# Water_Level_Sensor.net
KiCad netlist of a schematic drawn in EAGLE
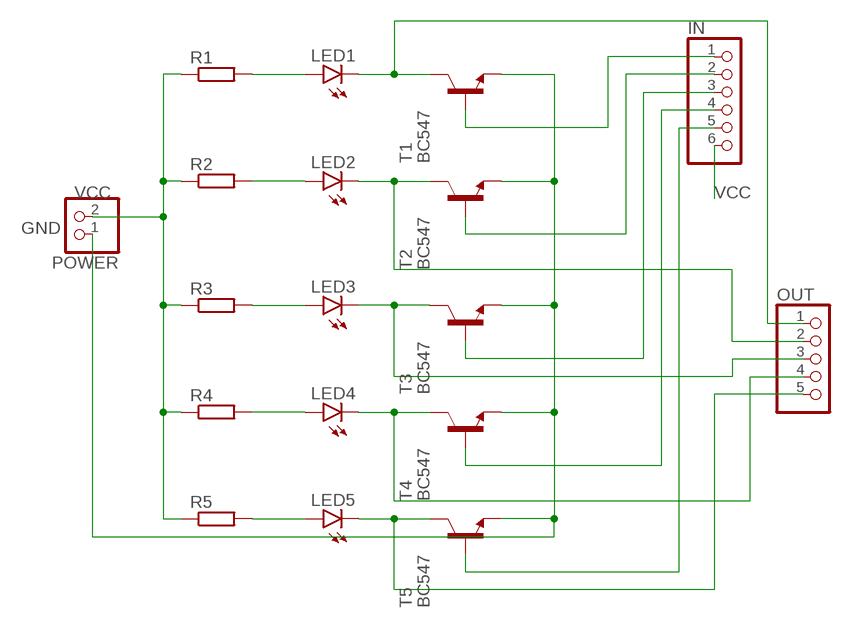
[diagram p0: schematic, sheet 1]

(export (version "E")
  (design (tool "Eeschema 10.0.6"))
  (components
    (comp (ref "IN")
      (value "PINHD-1X6")
      (footprint "eagle-import:1X06")
      (libsource (lib "eagle-import") (part "PINHD-1X6"))
    )
    (comp (ref "LED1")
      (value "LED5MM")
      (footprint "eagle-import:LED5MM")
      (libsource (lib "eagle-import") (part "LED5MM"))
    )
    (comp (ref "LED2")
      (value "LED5MM")
      (footprint "eagle-import:LED5MM")
      (libsource (lib "eagle-import") (part "LED5MM"))
    )
    (comp (ref "LED3")
      (value "LED5MM")
      (footprint "eagle-import:LED5MM")
      (libsource (lib "eagle-import") (part "LED5MM"))
    )
    (comp (ref "LED4")
      (value "LED5MM")
      (footprint "eagle-import:LED5MM")
      (libsource (lib "eagle-import") (part "LED5MM"))
    )
    (comp (ref "LED5")
      (value "LED5MM")
      (footprint "eagle-import:LED5MM")
      (libsource (lib "eagle-import") (part "LED5MM"))
    )
    (comp (ref "OUT")
      (value "PINHD-1X5")
      (footprint "eagle-import:1X05")
      (libsource (lib "eagle-import") (part "PINHD-1X5"))
    )
    (comp (ref "POWER")
      (value "PINHD-1X2")
      (footprint "eagle-import:1X02")
      (libsource (lib "eagle-import") (part "PINHD-1X2"))
    )
    (comp (ref "R1")
      (value "R-EU_0204/7")
      (footprint "eagle-import:0204_7")
      (libsource (lib "eagle-import") (part "R-EU_0204/7"))
    )
    (comp (ref "R2")
      (value "R-EU_0204/7")
      (footprint "eagle-import:0204_7")
      (libsource (lib "eagle-import") (part "R-EU_0204/7"))
    )
    (comp (ref "R3")
      (value "R-EU_0204/7")
      (footprint "eagle-import:0204_7")
      (libsource (lib "eagle-import") (part "R-EU_0204/7"))
    )
    (comp (ref "R4")
      (value "R-EU_0204/7")
      (footprint "eagle-import:0204_7")
      (libsource (lib "eagle-import") (part "R-EU_0204/7"))
    )
    (comp (ref "R5")
      (value "R-EU_0204/7")
      (footprint "eagle-import:0204_7")
      (libsource (lib "eagle-import") (part "R-EU_0204/7"))
    )
    (comp (ref "T1")
      (value "BC547")
      (footprint "eagle-import:TO92")
      (libsource (lib "eagle-import") (part "BC547"))
    )
    (comp (ref "T2")
      (value "BC547")
      (footprint "eagle-import:TO92")
      (libsource (lib "eagle-import") (part "BC547"))
    )
    (comp (ref "T3")
      (value "BC547")
      (footprint "eagle-import:TO92")
      (libsource (lib "eagle-import") (part "BC547"))
    )
    (comp (ref "T4")
      (value "BC547")
      (footprint "eagle-import:TO92")
      (libsource (lib "eagle-import") (part "BC547"))
    )
    (comp (ref "T5")
      (value "BC547")
      (footprint "eagle-import:TO92")
      (libsource (lib "eagle-import") (part "BC547"))
    )
  )
  (nets
    (net (code "1") (name "/GND") (class "Default")
      (node (ref "POWER") (pin "1") (pinfunction "1_1") (pintype "passive"))
      (node (ref "T1") (pin "1") (pinfunction "E_1") (pintype "passive"))
      (node (ref "T2") (pin "1") (pinfunction "E_1") (pintype "passive"))
      (node (ref "T3") (pin "1") (pinfunction "E_1") (pintype "passive"))
      (node (ref "T4") (pin "1") (pinfunction "E_1") (pintype "passive"))
      (node (ref "T5") (pin "1") (pinfunction "E_1") (pintype "passive"))
    )
    (net (code "2") (name "/VCC") (class "Default")
      (node (ref "IN") (pin "6") (pinfunction "6_6") (pintype "passive"))
      (node (ref "POWER") (pin "2") (pinfunction "2_2") (pintype "passive"))
      (node (ref "R1") (pin "1") (pinfunction "1_1") (pintype "passive"))
      (node (ref "R2") (pin "1") (pinfunction "1_1") (pintype "passive"))
      (node (ref "R3") (pin "1") (pinfunction "1_1") (pintype "passive"))
      (node (ref "R4") (pin "1") (pinfunction "1_1") (pintype "passive"))
      (node (ref "R5") (pin "1") (pinfunction "1_1") (pintype "passive"))
    )
    (net (code "3") (name "Net-(LED1-C)") (class "Default")
      (node (ref "LED1") (pin "K") (pinfunction "C_K") (pintype "passive"))
      (node (ref "OUT") (pin "1") (pinfunction "1_1") (pintype "passive"))
      (node (ref "T1") (pin "3") (pinfunction "C_3") (pintype "passive"))
    )
    (net (code "4") (name "Net-(LED1-PadA)") (class "Default")
      (node (ref "LED1") (pin "A") (pinfunction "A_A") (pintype "passive"))
      (node (ref "R1") (pin "2") (pinfunction "2_2") (pintype "passive"))
    )
    (net (code "5") (name "Net-(LED2-C)") (class "Default")
      (node (ref "LED2") (pin "K") (pinfunction "C_K") (pintype "passive"))
      (node (ref "OUT") (pin "2") (pinfunction "2_2") (pintype "passive"))
      (node (ref "T2") (pin "3") (pinfunction "C_3") (pintype "passive"))
    )
    (net (code "6") (name "Net-(LED2-PadA)") (class "Default")
      (node (ref "LED2") (pin "A") (pinfunction "A_A") (pintype "passive"))
      (node (ref "R2") (pin "2") (pinfunction "2_2") (pintype "passive"))
    )
    (net (code "7") (name "Net-(LED3-C)") (class "Default")
      (node (ref "LED3") (pin "K") (pinfunction "C_K") (pintype "passive"))
      (node (ref "OUT") (pin "3") (pinfunction "3_3") (pintype "passive"))
      (node (ref "T3") (pin "3") (pinfunction "C_3") (pintype "passive"))
    )
    (net (code "8") (name "Net-(LED3-PadA)") (class "Default")
      (node (ref "LED3") (pin "A") (pinfunction "A_A") (pintype "passive"))
      (node (ref "R3") (pin "2") (pinfunction "2_2") (pintype "passive"))
    )
    (net (code "9") (name "Net-(LED4-C)") (class "Default")
      (node (ref "LED4") (pin "K") (pinfunction "C_K") (pintype "passive"))
      (node (ref "OUT") (pin "4") (pinfunction "4_4") (pintype "passive"))
      (node (ref "T4") (pin "3") (pinfunction "C_3") (pintype "passive"))
    )
    (net (code "10") (name "Net-(LED4-PadA)") (class "Default")
      (node (ref "LED4") (pin "A") (pinfunction "A_A") (pintype "passive"))
      (node (ref "R4") (pin "2") (pinfunction "2_2") (pintype "passive"))
    )
    (net (code "11") (name "Net-(LED5-C)") (class "Default")
      (node (ref "LED5") (pin "K") (pinfunction "C_K") (pintype "passive"))
      (node (ref "OUT") (pin "5") (pinfunction "5_5") (pintype "passive"))
      (node (ref "T5") (pin "3") (pinfunction "C_3") (pintype "passive"))
    )
    (net (code "12") (name "Net-(LED5-PadA)") (class "Default")
      (node (ref "LED5") (pin "A") (pinfunction "A_A") (pintype "passive"))
      (node (ref "R5") (pin "2") (pinfunction "2_2") (pintype "passive"))
    )
    (net (code "13") (name "Net-(T1-B)") (class "Default")
      (node (ref "IN") (pin "1") (pinfunction "1_1") (pintype "passive"))
      (node (ref "T1") (pin "2") (pinfunction "B_2") (pintype "passive"))
    )
    (net (code "14") (name "Net-(T2-B)") (class "Default")
      (node (ref "IN") (pin "2") (pinfunction "2_2") (pintype "passive"))
      (node (ref "T2") (pin "2") (pinfunction "B_2") (pintype "passive"))
    )
    (net (code "15") (name "Net-(T3-B)") (class "Default")
      (node (ref "IN") (pin "3") (pinfunction "3_3") (pintype "passive"))
      (node (ref "T3") (pin "2") (pinfunction "B_2") (pintype "passive"))
    )
    (net (code "16") (name "Net-(T4-B)") (class "Default")
      (node (ref "IN") (pin "4") (pinfunction "4_4") (pintype "passive"))
      (node (ref "T4") (pin "2") (pinfunction "B_2") (pintype "passive"))
    )
    (net (code "17") (name "Net-(T5-B)") (class "Default")
      (node (ref "IN") (pin "5") (pinfunction "5_5") (pintype "passive"))
      (node (ref "T5") (pin "2") (pinfunction "B_2") (pintype "passive"))
    )
  )
)
